# power-io.net
KiCad netlist of a schematic drawn in Altium Designer
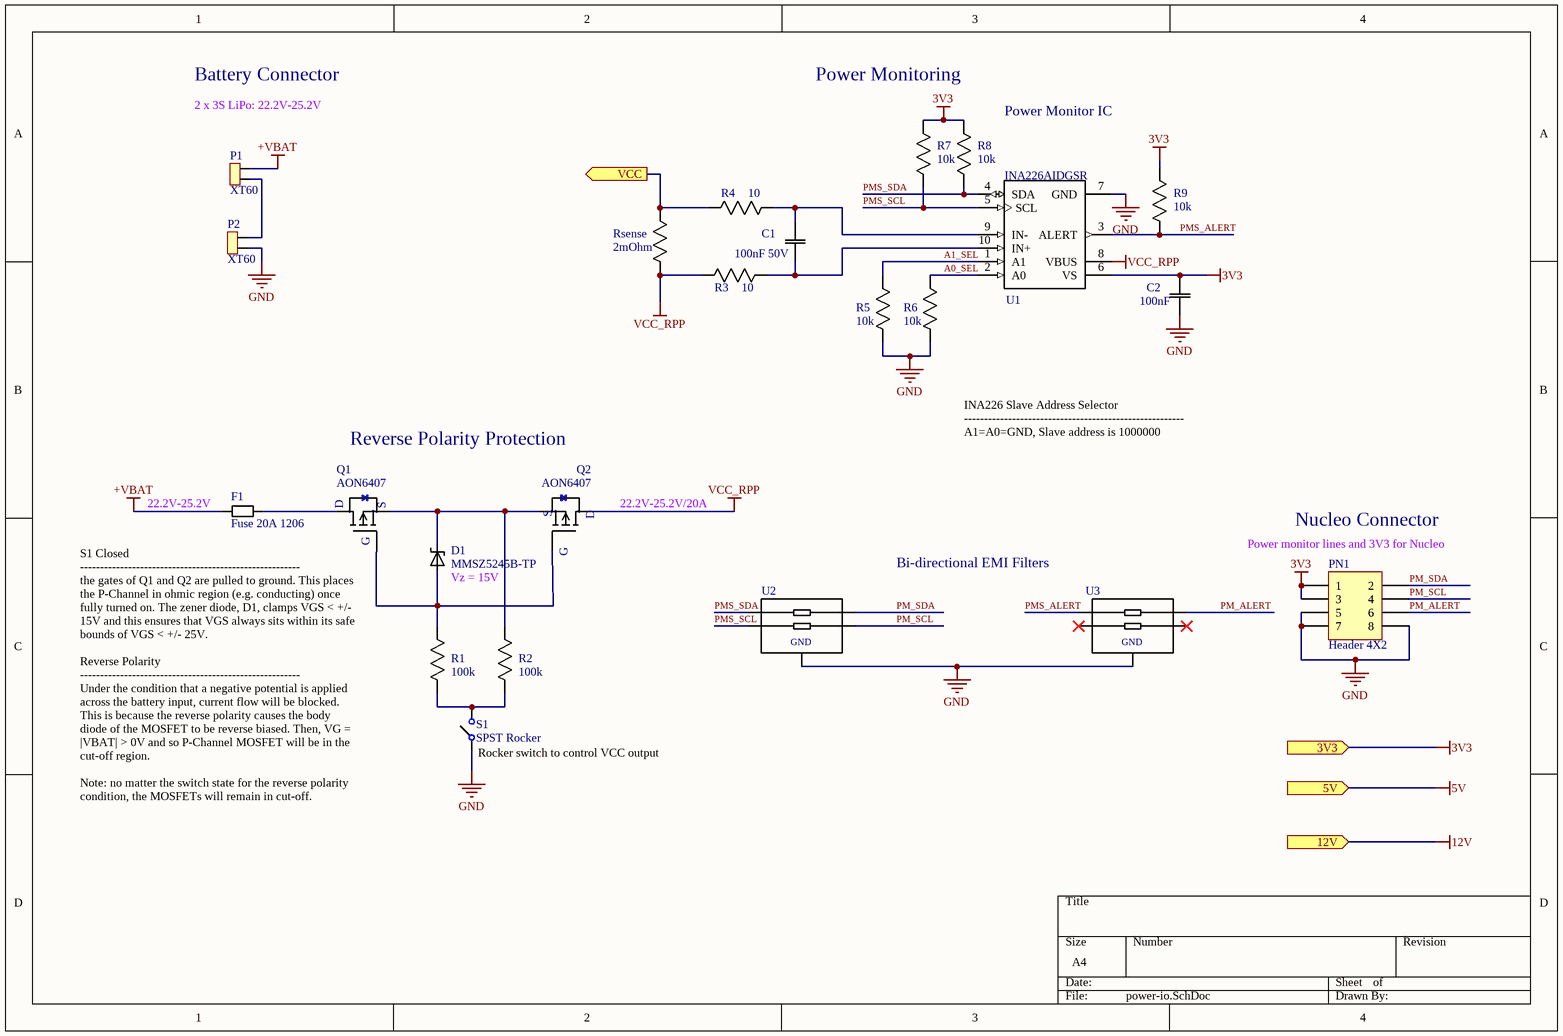
[diagram p0: power-io.SchDoc]

(export (version "E")
  (design (tool "Eeschema 10.0.6"))
  (components
    (comp (ref "C1")
      (value "100nF 50V")
      (footprint "0805")
      (description "CAP CER 0.1UF 50V X7R 0805")
      (fields (field (name "MP") "CC0805KRX7R9BB104") (field (name "MF") "Yageo"))
      (libsource (lib "AltiumLibraries") (part "CAP 100nF 0805"))
    )
    (comp (ref "C2")
      (value "100nF")
      (footprint "0805")
      (description "CAP CER 0.1UF 50V X7R 0805")
      (fields (field (name "MP") "CC0805KRX7R9BB104") (field (name "MF") "Yageo"))
      (libsource (lib "AltiumLibraries") (part "CAP 100nF 0805"))
    )
    (comp (ref "D1")
      (value "MMSZ5245B-TP")
      (footprint "SOD-123")
      (description "Zener Diode 15V 500mW ±5% Surface Mount SOD-123")
      (fields (field (name "MP") "MMSZ5224BT1G") (field (name "MF") "ON Semiconductor"))
      (libsource (lib "AltiumLibraries") (part "MMSZ5245B-TP"))
    )
    (comp (ref "F1")
      (value "Fuse 20A 1206")
      (footprint "1206")
      (description "FUSE BOARD MOUNT 20A 32VAC 63VDC")
      (fields (field (name "MF") "Schurter Inc.") (field (name "MP") "3413.0331.22"))
      (libsource (lib "AltiumLibraries") (part "Fuse 20A 1206"))
    )
    (comp (ref "P1")
      (value "XT60")
      (footprint "XT60Connector")
      (description "XT60 CONNECTORS FEMALE PAIR")
      (fields (field (name "MF") "SparkFun Electronics") (field (name "MP") "PRT-10474"))
      (libsource (lib "AltiumLibraries") (part "XT60 Connector"))
    )
    (comp (ref "P2")
      (value "XT60")
      (footprint "XT60Connector")
      (description "XT60 CONNECTORS FEMALE PAIR")
      (fields (field (name "MF") "SparkFun Electronics") (field (name "MP") "PRT-10474"))
      (libsource (lib "AltiumLibraries") (part "XT60 Connector"))
    )
    (comp (ref "PN1")
      (value "Header 4X2")
      (footprint "HDR2X4")
      (description "Header, 4-Pin, Dual row")
      (fields (field (name "PUBLISHER") "Altium Limited"))
      (libsource (lib "Miscellaneous Connectors") (part "Header 4X2"))
    )
    (comp (ref "Q1")
      (value "AON6407")
      (footprint "8-PowerSMD")
      (description "P-Channel 30V 32A (Ta), 85A (Tc) 7.3W (Ta), 83W (Tc) Surface Mount 8-DFN (5x6)")
      (fields (field (name "MF") "Alpha & Omega Semiconductor Inc."))
      (libsource (lib "AltiumLibraries") (part "AON6407"))
    )
    (comp (ref "Q2")
      (value "AON6407")
      (footprint "8-PowerSMD")
      (description "P-Channel 30V 32A (Ta), 85A (Tc) 7.3W (Ta), 83W (Tc) Surface Mount 8-DFN (5x6)")
      (fields (field (name "MF") "Alpha & Omega Semiconductor Inc."))
      (libsource (lib "AltiumLibraries") (part "AON6407"))
    )
    (comp (ref "R1")
      (value "100k")
      (footprint "0805")
      (description "RES SMD 100K OHM 1% 1/8W 0805")
      (fields (field (name "MP") "RC0805FR-07100KL") (field (name "MF") "Yageo"))
      (libsource (lib "AltiumLibraries") (part "RES 100k 0805"))
    )
    (comp (ref "R2")
      (value "100k")
      (footprint "0805")
      (description "RES SMD 100K OHM 1% 1/8W 0805")
      (fields (field (name "MP") "RC0805FR-07100KL") (field (name "MF") "Yageo"))
      (libsource (lib "AltiumLibraries") (part "RES 100k 0805"))
    )
    (comp (ref "R3")
      (value "10")
      (footprint "0805")
      (description "RES SMD 10 OHM 1% 1/8W 0805")
      (fields (field (name "MP") "RC0805FR-0710RL") (field (name "MF") "Yageo"))
      (libsource (lib "AltiumLibraries") (part "RES 10 0805"))
    )
    (comp (ref "R4")
      (value "10")
      (footprint "0805")
      (description "RES SMD 10 OHM 1% 1/8W 0805")
      (fields (field (name "MP") "RC0805FR-0710RL") (field (name "MF") "Yageo"))
      (libsource (lib "AltiumLibraries") (part "RES 10 0805"))
    )
    (comp (ref "R5")
      (value "10k")
      (footprint "0805")
      (description "RES SMD 10K OHM 1% 1/8W 0805")
      (fields (field (name "TOLERANCE") "1%"))
      (libsource (lib "AltiumLibraries") (part "RES 10k 1/8W"))
    )
    (comp (ref "R6")
      (value "10k")
      (footprint "0805")
      (description "RES SMD 10K OHM 1% 1/8W 0805")
      (fields (field (name "TOLERANCE") "1%"))
      (libsource (lib "AltiumLibraries") (part "RES 10k 1/8W"))
    )
    (comp (ref "R7")
      (value "10k")
      (footprint "0805")
      (description "RES SMD 10K OHM 1% 1/8W 0805")
      (fields (field (name "MP") "RC0805FR-0710KL") (field (name "MF") "Yageo"))
      (libsource (lib "AltiumLibraries") (part "RES 10k 0805"))
    )
    (comp (ref "R8")
      (value "10k")
      (footprint "0805")
      (description "RES SMD 10K OHM 1% 1/8W 0805")
      (fields (field (name "MP") "RC0805FR-0710KL") (field (name "MF") "Yageo"))
      (libsource (lib "AltiumLibraries") (part "RES 10k 0805"))
    )
    (comp (ref "R9")
      (value "10k")
      (footprint "0805")
      (description "RES SMD 10K OHM 1% 1/8W 0805")
      (fields (field (name "MP") "RC0805FR-0710KL") (field (name "MF") "Yageo"))
      (libsource (lib "AltiumLibraries") (part "RES 10k 0805"))
    )
    (comp (ref "Rsense")
      (value "2mOhm")
      (footprint "1206")
      (description "RES 0.002 OHM 1% 1W 1206")
      (fields (field (name "MP") "CSR1206-0R002F1") (field (name "MF") "Riedon"))
      (libsource (lib "AltiumLibraries") (part "RES 2mOhm 1206"))
    )
    (comp (ref "S1")
      (value "SPST Rocker")
      (footprint "SWITCH ROCKER SPST 10A 125V")
      (description "Rocker Switch SPST 10A (AC) 125V Panel Mount, Snap-In")
      (fields (field (name "MP") "SRB22A2FBBNN") (field (name "MF") "ZF Electronics"))
      (libsource (lib "AltiumLibraries") (part "SWITCH ROCKER SPST 10A 125V"))
    )
    (comp (ref "U1")
      (value "INA226AIDGSR")
      (footprint "10-VSSOP")
      (fields (field (name "MF") "Texas Instruments"))
      (libsource (lib "AltiumLibraries") (part "INA226AIDGSR"))
    )
    (comp (ref "U2")
      (value "EMI")
      (footprint "SOT-665")
      (description "RC (Pi) EMI Filter 2nd Order Low Pass 2 Channel R = 100Ohms, C = 19pF (Total)  SOT-665")
      (fields (field (name "MF") "Nexperia USA Inc.") (field (name "MP") "IP4256CZ5-W,115"))
      (libsource (lib "AltiumLibraries") (part "IP4256CZ5-W"))
    )
    (comp (ref "U3")
      (value "EMI")
      (footprint "SOT-665")
      (description "RC (Pi) EMI Filter 2nd Order Low Pass 2 Channel R = 100Ohms, C = 19pF (Total)  SOT-665")
      (fields (field (name "MF") "Nexperia USA Inc.") (field (name "MP") "IP4256CZ5-W,115"))
      (libsource (lib "AltiumLibraries") (part "IP4256CZ5-W"))
    )
  )
  (nets
    (net (code "1") (name "+VBAT") (class "Default")
      (node (ref "F1") (pin "1") (pinfunction "1_1") (pintype "passive"))
      (node (ref "P1") (pin "2") (pinfunction "2_2") (pintype "passive"))
    )
    (net (code "2") (name "/A0_SEL") (class "Default")
      (node (ref "R6") (pin "1") (pinfunction "R1_1") (pintype "passive"))
      (node (ref "U1") (pin "2") (pinfunction "A0_2") (pintype "input"))
    )
    (net (code "3") (name "/A1_SEL") (class "Default")
      (node (ref "R5") (pin "1") (pinfunction "R1_1") (pintype "passive"))
      (node (ref "U1") (pin "1") (pinfunction "A1_1") (pintype "input"))
    )
    (net (code "4") (name "/PMS_ALERT") (class "Default")
      (node (ref "R9") (pin "2") (pinfunction "R2_2") (pintype "passive"))
      (node (ref "U1") (pin "3") (pinfunction "ALERT_3") (pintype "output"))
      (node (ref "U3") (pin "1") (pinfunction "P$1_1") (pintype "passive"))
    )
    (net (code "5") (name "/PMS_SCL") (class "Default")
      (node (ref "R7") (pin "2") (pinfunction "R2_2") (pintype "passive"))
      (node (ref "U1") (pin "5") (pinfunction "SCL_5") (pintype "input"))
      (node (ref "U2") (pin "3") (pinfunction "P$3_3") (pintype "passive"))
    )
    (net (code "6") (name "/PMS_SDA") (class "Default")
      (node (ref "R8") (pin "2") (pinfunction "R2_2") (pintype "passive"))
      (node (ref "U1") (pin "4") (pinfunction "SDA_4") (pintype "bidirectional"))
      (node (ref "U2") (pin "1") (pinfunction "P$1_1") (pintype "passive"))
    )
    (net (code "7") (name "/PM_ALERT") (class "Default")
      (node (ref "PN1") (pin "6") (pinfunction "6_6") (pintype "passive"))
      (node (ref "U3") (pin "5") (pinfunction "P$5_5") (pintype "passive"))
    )
    (net (code "8") (name "/PM_SCL") (class "Default")
      (node (ref "PN1") (pin "4") (pinfunction "4_4") (pintype "passive"))
      (node (ref "U2") (pin "4") (pinfunction "P$4_4") (pintype "passive"))
    )
    (net (code "9") (name "/PM_SDA") (class "Default")
      (node (ref "PN1") (pin "2") (pinfunction "2_2") (pintype "passive"))
      (node (ref "U2") (pin "5") (pinfunction "P$5_5") (pintype "passive"))
    )
    (net (code "10") (name "/VCC") (class "Default")
      (node (ref "R4") (pin "2") (pinfunction "R2_2") (pintype "passive"))
      (node (ref "Rsense") (pin "1") (pinfunction "R1_1") (pintype "passive"))
    )
    (net (code "11") (name "3V3") (class "Default")
      (node (ref "C2") (pin "2") (pinfunction "C2_2") (pintype "passive"))
      (node (ref "PN1") (pin "1") (pinfunction "1_1") (pintype "passive"))
      (node (ref "PN1") (pin "3") (pinfunction "3_3") (pintype "passive"))
      (node (ref "R7") (pin "1") (pinfunction "R1_1") (pintype "passive"))
      (node (ref "R8") (pin "1") (pinfunction "R1_1") (pintype "passive"))
      (node (ref "R9") (pin "1") (pinfunction "R1_1") (pintype "passive"))
      (node (ref "U1") (pin "6") (pinfunction "VS_6") (pintype "power_in"))
    )
    (net (code "14") (name "GND") (class "Default")
      (node (ref "C2") (pin "1") (pinfunction "C1_1") (pintype "passive"))
      (node (ref "P2") (pin "1") (pinfunction "1_1") (pintype "passive"))
      (node (ref "PN1") (pin "5") (pinfunction "5_5") (pintype "passive"))
      (node (ref "PN1") (pin "7") (pinfunction "7_7") (pintype "passive"))
      (node (ref "PN1") (pin "8") (pinfunction "8_8") (pintype "passive"))
      (node (ref "R5") (pin "2") (pinfunction "R2_2") (pintype "passive"))
      (node (ref "R6") (pin "2") (pinfunction "R2_2") (pintype "passive"))
      (node (ref "S1") (pin "0") (pinfunction "0_0") (pintype "passive"))
      (node (ref "U1") (pin "7") (pinfunction "GND_7") (pintype "power_in"))
      (node (ref "U2") (pin "2") (pinfunction "P$2_2") (pintype "passive"))
      (node (ref "U3") (pin "2") (pinfunction "P$2_2") (pintype "passive"))
    )
    (net (code "15") (name "Net-(C1-C1)") (class "Default")
      (node (ref "C1") (pin "1") (pinfunction "C1_1") (pintype "passive"))
      (node (ref "R3") (pin "1") (pinfunction "R1_1") (pintype "passive"))
      (node (ref "U1") (pin "10") (pinfunction "IN+_10") (pintype "input"))
    )
    (net (code "16") (name "Net-(C1-C2)") (class "Default")
      (node (ref "C1") (pin "2") (pinfunction "C2_2") (pintype "passive"))
      (node (ref "R4") (pin "1") (pinfunction "R1_1") (pintype "passive"))
      (node (ref "U1") (pin "9") (pinfunction "IN-_9") (pintype "input"))
    )
    (net (code "17") (name "Net-(F1-Pad2)") (class "Default")
      (node (ref "F1") (pin "2") (pinfunction "2_2") (pintype "passive"))
      (node (ref "Q1") (pin "D") (pinfunction "D_D") (pintype "passive"))
    )
    (net (code "18") (name "Net-(P1-Pad1)") (class "Default")
      (node (ref "P1") (pin "1") (pinfunction "1_1") (pintype "passive"))
      (node (ref "P2") (pin "2") (pinfunction "2_2") (pintype "passive"))
    )
    (net (code "19") (name "Net-(R1-R1)") (class "Default")
      (node (ref "D1") (pin "A") (pinfunction "A_A") (pintype "passive"))
      (node (ref "Q1") (pin "G") (pinfunction "G_G") (pintype "passive"))
      (node (ref "Q2") (pin "G") (pinfunction "G_G") (pintype "passive"))
      (node (ref "R1") (pin "1") (pinfunction "R1_1") (pintype "passive"))
    )
    (net (code "20") (name "Net-(R1-R2)") (class "Default")
      (node (ref "R1") (pin "2") (pinfunction "R2_2") (pintype "passive"))
      (node (ref "R2") (pin "2") (pinfunction "R2_2") (pintype "passive"))
      (node (ref "S1") (pin "1") (pinfunction "1_1") (pintype "passive"))
    )
    (net (code "21") (name "Net-(R2-R1)") (class "Default")
      (node (ref "D1") (pin "C") (pinfunction "C_C") (pintype "passive"))
      (node (ref "Q1") (pin "S") (pinfunction "S_S") (pintype "passive"))
      (node (ref "Q2") (pin "S") (pinfunction "S_S") (pintype "passive"))
      (node (ref "R2") (pin "1") (pinfunction "R1_1") (pintype "passive"))
    )
    (net (code "22") (name "VCC_RPP") (class "Default")
      (node (ref "Q2") (pin "D") (pinfunction "D_D") (pintype "passive"))
      (node (ref "R3") (pin "2") (pinfunction "R2_2") (pintype "passive"))
      (node (ref "Rsense") (pin "2") (pinfunction "R2_2") (pintype "passive"))
      (node (ref "U1") (pin "8") (pinfunction "VBUS_8") (pintype "power_in"))
    )
    (net (code "23") (name "unconnected-(U3-P$3-Pad3)") (class "Default")
      (node (ref "U3") (pin "3") (pinfunction "P$3_3") (pintype "passive+no_connect"))
    )
    (net (code "24") (name "unconnected-(U3-P$4-Pad4)") (class "Default")
      (node (ref "U3") (pin "4") (pinfunction "P$4_4") (pintype "passive+no_connect"))
    )
  )
)
